# AMS_balancing.net
KiCad netlist of a schematic drawn in Altium Designer
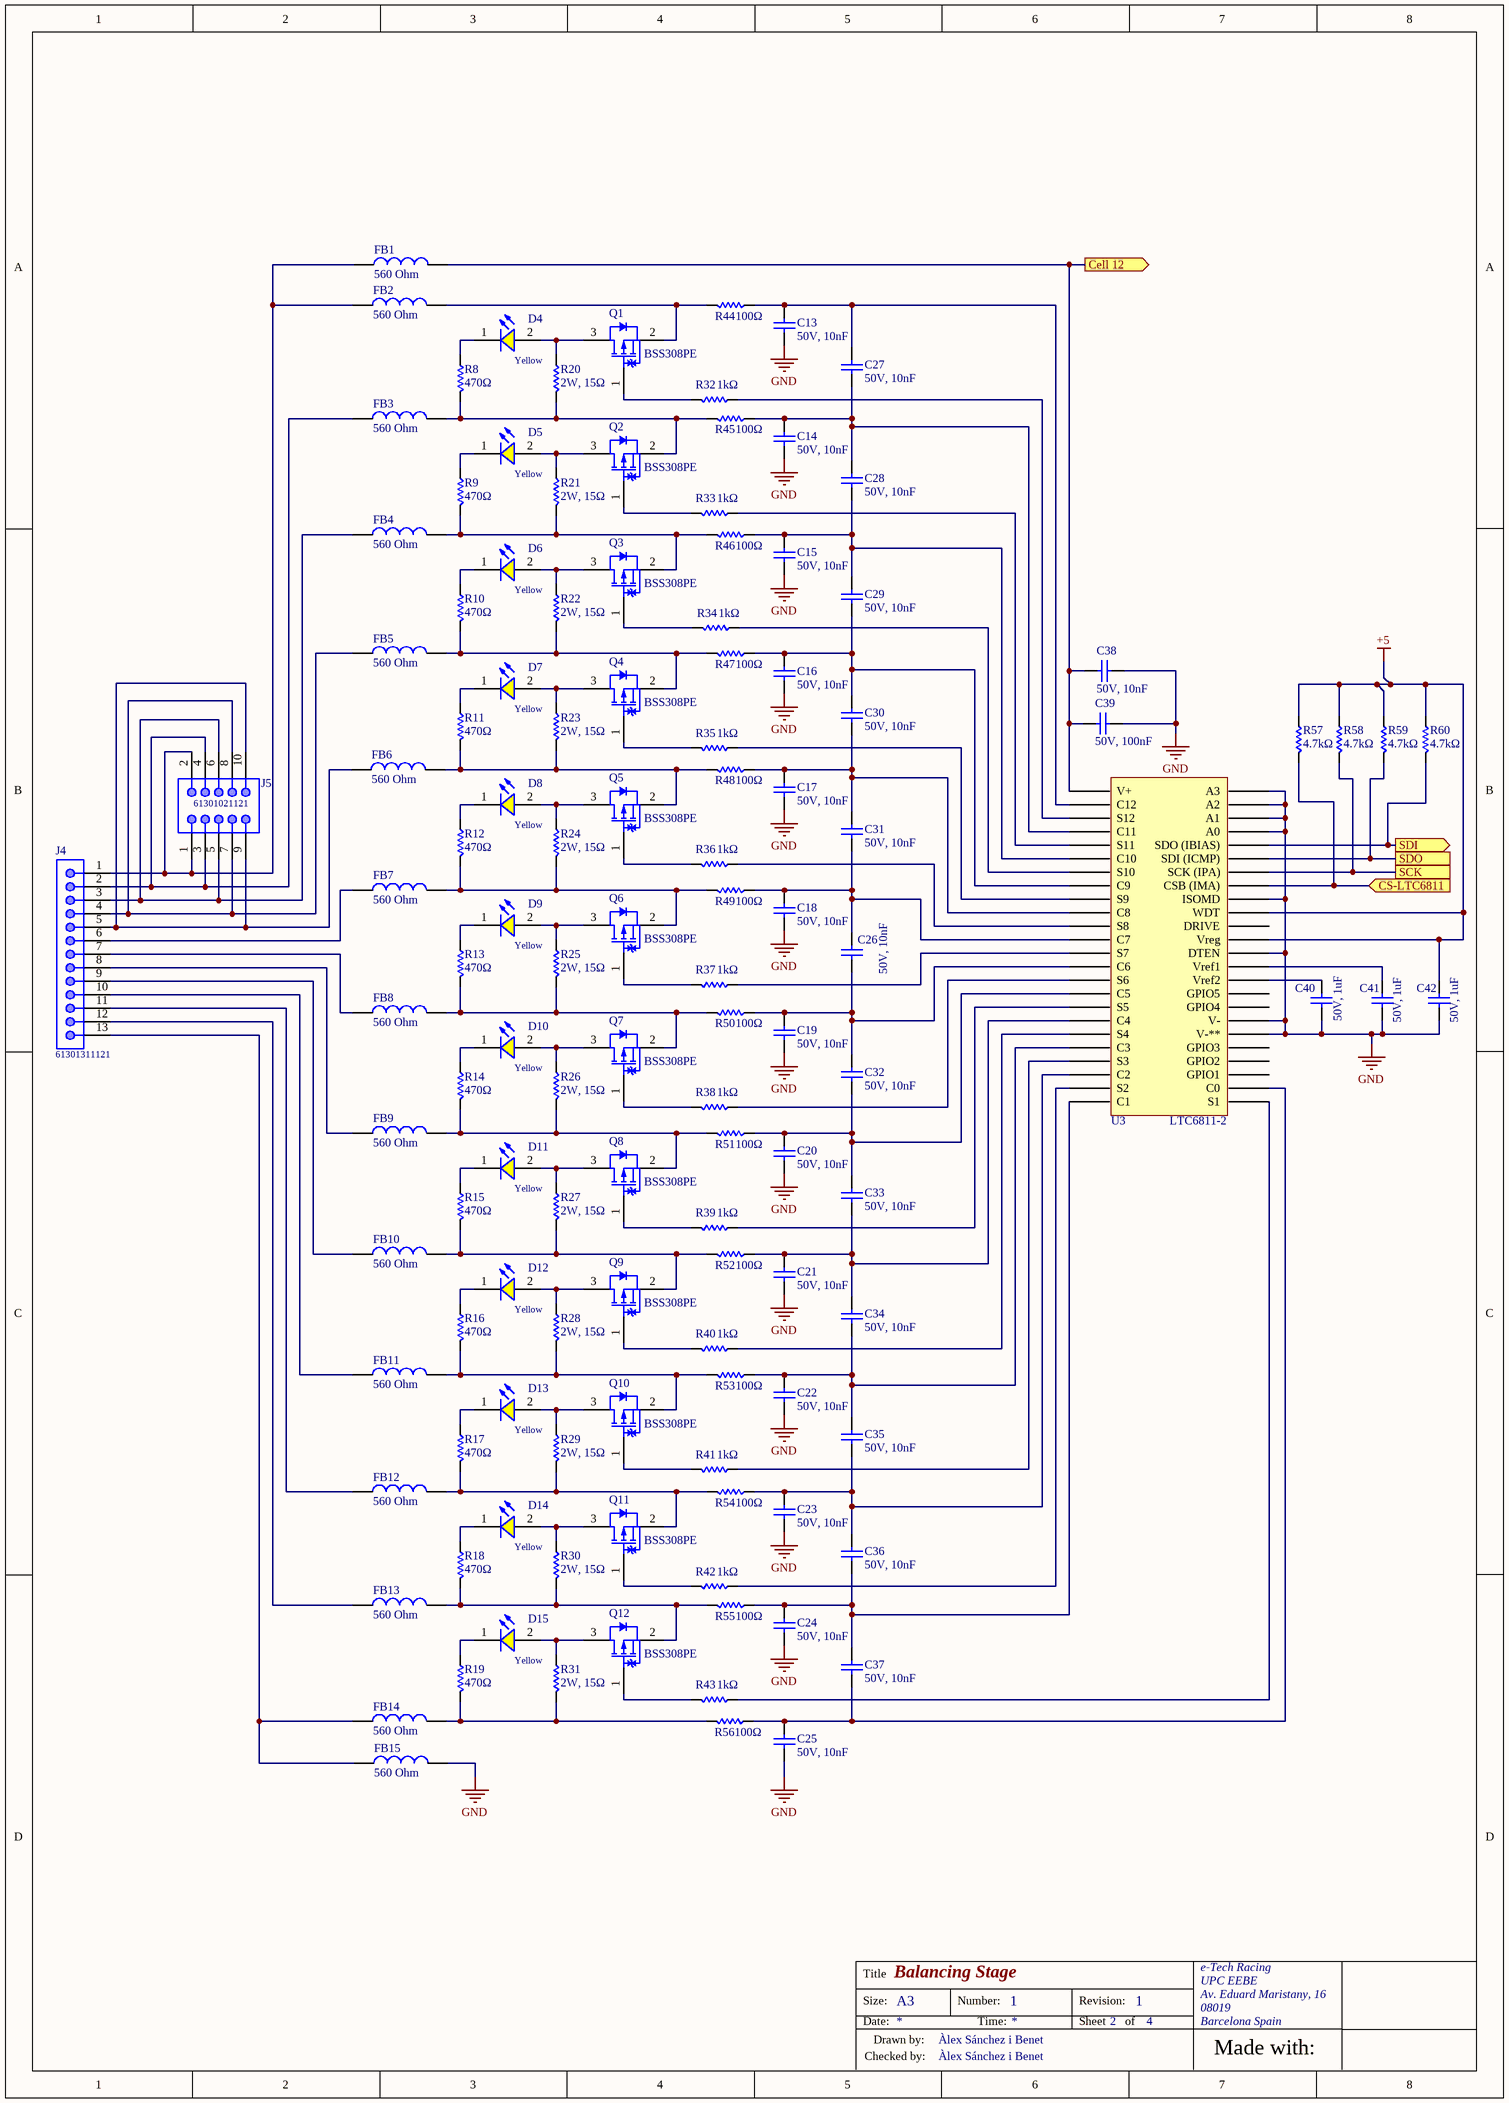
[diagram p0: AMS_balancing.SchDoc]

(export (version "E")
  (design (tool "Eeschema 10.0.6"))
  (components
    (comp (ref "C13")
      (value "50V, 10nF")
      (footprint "0805_2x1.25x0.8mm_Reflow Soldering")
      (description "WCAP-CSGP Ceramic Capacitors, 0805, X7R, 50V, 10nF")
      (fields (field (name "PART NUMBER") "885012207092") (field (name "PUBLISHER") "Wurth Elektronik"))
      (libsource (lib "Components_Library") (part "885012207092"))
    )
    (comp (ref "C14")
      (value "50V, 10nF")
      (footprint "0805_2x1.25x0.8mm_Reflow Soldering")
      (description "WCAP-CSGP Ceramic Capacitors, 0805, X7R, 50V, 10nF")
      (fields (field (name "PART NUMBER") "885012207092") (field (name "PUBLISHER") "Wurth Elektronik"))
      (libsource (lib "Components_Library") (part "885012207092"))
    )
    (comp (ref "C15")
      (value "50V, 10nF")
      (footprint "0805_2x1.25x0.8mm_Reflow Soldering")
      (description "WCAP-CSGP Ceramic Capacitors, 0805, X7R, 50V, 10nF")
      (fields (field (name "PART NUMBER") "885012207092") (field (name "PUBLISHER") "Wurth Elektronik"))
      (libsource (lib "Components_Library") (part "885012207092"))
    )
    (comp (ref "C16")
      (value "50V, 10nF")
      (footprint "0805_2x1.25x0.8mm_Reflow Soldering")
      (description "WCAP-CSGP Ceramic Capacitors, 0805, X7R, 50V, 10nF")
      (fields (field (name "PART NUMBER") "885012207092") (field (name "PUBLISHER") "Wurth Elektronik"))
      (libsource (lib "Components_Library") (part "885012207092"))
    )
    (comp (ref "C17")
      (value "50V, 10nF")
      (footprint "0805_2x1.25x0.8mm_Reflow Soldering")
      (description "WCAP-CSGP Ceramic Capacitors, 0805, X7R, 50V, 10nF")
      (fields (field (name "PART NUMBER") "885012207092") (field (name "PUBLISHER") "Wurth Elektronik"))
      (libsource (lib "Components_Library") (part "885012207092"))
    )
    (comp (ref "C18")
      (value "50V, 10nF")
      (footprint "0805_2x1.25x0.8mm_Reflow Soldering")
      (description "WCAP-CSGP Ceramic Capacitors, 0805, X7R, 50V, 10nF")
      (fields (field (name "PART NUMBER") "885012207092") (field (name "PUBLISHER") "Wurth Elektronik"))
      (libsource (lib "Components_Library") (part "885012207092"))
    )
    (comp (ref "C19")
      (value "50V, 10nF")
      (footprint "0805_2x1.25x0.8mm_Reflow Soldering")
      (description "WCAP-CSGP Ceramic Capacitors, 0805, X7R, 50V, 10nF")
      (fields (field (name "PART NUMBER") "885012207092") (field (name "PUBLISHER") "Wurth Elektronik"))
      (libsource (lib "Components_Library") (part "885012207092"))
    )
    (comp (ref "C20")
      (value "50V, 10nF")
      (footprint "0805_2x1.25x0.8mm_Reflow Soldering")
      (description "WCAP-CSGP Ceramic Capacitors, 0805, X7R, 50V, 10nF")
      (fields (field (name "PART NUMBER") "885012207092") (field (name "PUBLISHER") "Wurth Elektronik"))
      (libsource (lib "Components_Library") (part "885012207092"))
    )
    (comp (ref "C21")
      (value "50V, 10nF")
      (footprint "0805_2x1.25x0.8mm_Reflow Soldering")
      (description "WCAP-CSGP Ceramic Capacitors, 0805, X7R, 50V, 10nF")
      (fields (field (name "PART NUMBER") "885012207092") (field (name "PUBLISHER") "Wurth Elektronik"))
      (libsource (lib "Components_Library") (part "885012207092"))
    )
    (comp (ref "C22")
      (value "50V, 10nF")
      (footprint "0805_2x1.25x0.8mm_Reflow Soldering")
      (description "WCAP-CSGP Ceramic Capacitors, 0805, X7R, 50V, 10nF")
      (fields (field (name "PART NUMBER") "885012207092") (field (name "PUBLISHER") "Wurth Elektronik"))
      (libsource (lib "Components_Library") (part "885012207092"))
    )
    (comp (ref "C23")
      (value "50V, 10nF")
      (footprint "0805_2x1.25x0.8mm_Reflow Soldering")
      (description "WCAP-CSGP Ceramic Capacitors, 0805, X7R, 50V, 10nF")
      (fields (field (name "PART NUMBER") "885012207092") (field (name "PUBLISHER") "Wurth Elektronik"))
      (libsource (lib "Components_Library") (part "885012207092"))
    )
    (comp (ref "C24")
      (value "50V, 10nF")
      (footprint "0805_2x1.25x0.8mm_Reflow Soldering")
      (description "WCAP-CSGP Ceramic Capacitors, 0805, X7R, 50V, 10nF")
      (fields (field (name "PART NUMBER") "885012207092") (field (name "PUBLISHER") "Wurth Elektronik"))
      (libsource (lib "Components_Library") (part "885012207092"))
    )
    (comp (ref "C25")
      (value "50V, 10nF")
      (footprint "0805_2x1.25x0.8mm_Reflow Soldering")
      (description "WCAP-CSGP Ceramic Capacitors, 0805, X7R, 50V, 10nF")
      (fields (field (name "PART NUMBER") "885012207092") (field (name "PUBLISHER") "Wurth Elektronik"))
      (libsource (lib "Components_Library") (part "885012207092"))
    )
    (comp (ref "C26")
      (value "50V, 10nF")
      (footprint "0805_2x1.25x0.8mm_Reflow Soldering")
      (description "WCAP-CSGP Ceramic Capacitors, 0805, X7R, 50V, 10nF")
      (fields (field (name "PART NUMBER") "885012207092") (field (name "PUBLISHER") "Wurth Elektronik"))
      (libsource (lib "Components_Library") (part "885012207092"))
    )
    (comp (ref "C27")
      (value "50V, 10nF")
      (footprint "0805_2x1.25x0.8mm_Reflow Soldering")
      (description "WCAP-CSGP Ceramic Capacitors, 0805, X7R, 50V, 10nF")
      (fields (field (name "PART NUMBER") "885012207092") (field (name "PUBLISHER") "Wurth Elektronik"))
      (libsource (lib "Components_Library") (part "885012207092"))
    )
    (comp (ref "C28")
      (value "50V, 10nF")
      (footprint "0805_2x1.25x0.8mm_Reflow Soldering")
      (description "WCAP-CSGP Ceramic Capacitors, 0805, X7R, 50V, 10nF")
      (fields (field (name "PART NUMBER") "885012207092") (field (name "PUBLISHER") "Wurth Elektronik"))
      (libsource (lib "Components_Library") (part "885012207092"))
    )
    (comp (ref "C29")
      (value "50V, 10nF")
      (footprint "0805_2x1.25x0.8mm_Reflow Soldering")
      (description "WCAP-CSGP Ceramic Capacitors, 0805, X7R, 50V, 10nF")
      (fields (field (name "PART NUMBER") "885012207092") (field (name "PUBLISHER") "Wurth Elektronik"))
      (libsource (lib "Components_Library") (part "885012207092"))
    )
    (comp (ref "C30")
      (value "50V, 10nF")
      (footprint "0805_2x1.25x0.8mm_Reflow Soldering")
      (description "WCAP-CSGP Ceramic Capacitors, 0805, X7R, 50V, 10nF")
      (fields (field (name "PART NUMBER") "885012207092") (field (name "PUBLISHER") "Wurth Elektronik"))
      (libsource (lib "Components_Library") (part "885012207092"))
    )
    (comp (ref "C31")
      (value "50V, 10nF")
      (footprint "0805_2x1.25x0.8mm_Reflow Soldering")
      (description "WCAP-CSGP Ceramic Capacitors, 0805, X7R, 50V, 10nF")
      (fields (field (name "PART NUMBER") "885012207092") (field (name "PUBLISHER") "Wurth Elektronik"))
      (libsource (lib "Components_Library") (part "885012207092"))
    )
    (comp (ref "C32")
      (value "50V, 10nF")
      (footprint "0805_2x1.25x0.8mm_Reflow Soldering")
      (description "WCAP-CSGP Ceramic Capacitors, 0805, X7R, 50V, 10nF")
      (fields (field (name "PART NUMBER") "885012207092") (field (name "PUBLISHER") "Wurth Elektronik"))
      (libsource (lib "Components_Library") (part "885012207092"))
    )
    (comp (ref "C33")
      (value "50V, 10nF")
      (footprint "0805_2x1.25x0.8mm_Reflow Soldering")
      (description "WCAP-CSGP Ceramic Capacitors, 0805, X7R, 50V, 10nF")
      (fields (field (name "PART NUMBER") "885012207092") (field (name "PUBLISHER") "Wurth Elektronik"))
      (libsource (lib "Components_Library") (part "885012207092"))
    )
    (comp (ref "C34")
      (value "50V, 10nF")
      (footprint "0805_2x1.25x0.8mm_Reflow Soldering")
      (description "WCAP-CSGP Ceramic Capacitors, 0805, X7R, 50V, 10nF")
      (fields (field (name "PART NUMBER") "885012207092") (field (name "PUBLISHER") "Wurth Elektronik"))
      (libsource (lib "Components_Library") (part "885012207092"))
    )
    (comp (ref "C35")
      (value "50V, 10nF")
      (footprint "0805_2x1.25x0.8mm_Reflow Soldering")
      (description "WCAP-CSGP Ceramic Capacitors, 0805, X7R, 50V, 10nF")
      (fields (field (name "PART NUMBER") "885012207092") (field (name "PUBLISHER") "Wurth Elektronik"))
      (libsource (lib "Components_Library") (part "885012207092"))
    )
    (comp (ref "C36")
      (value "50V, 10nF")
      (footprint "0805_2x1.25x0.8mm_Reflow Soldering")
      (description "WCAP-CSGP Ceramic Capacitors, 0805, X7R, 50V, 10nF")
      (fields (field (name "PART NUMBER") "885012207092") (field (name "PUBLISHER") "Wurth Elektronik"))
      (libsource (lib "Components_Library") (part "885012207092"))
    )
    (comp (ref "C37")
      (value "50V, 10nF")
      (footprint "0805_2x1.25x0.8mm_Reflow Soldering")
      (description "WCAP-CSGP Ceramic Capacitors, 0805, X7R, 50V, 10nF")
      (fields (field (name "PART NUMBER") "885012207092") (field (name "PUBLISHER") "Wurth Elektronik"))
      (libsource (lib "Components_Library") (part "885012207092"))
    )
    (comp (ref "C38")
      (value "50V, 10nF")
      (footprint "0805_2x1.25x0.8mm_Reflow Soldering")
      (description "WCAP-CSGP Ceramic Capacitors, 0805, X7R, 50V, 10nF")
      (fields (field (name "PART NUMBER") "885012207092") (field (name "PUBLISHER") "Wurth Elektronik"))
      (libsource (lib "Components_Library") (part "885012207092"))
    )
    (comp (ref "C39")
      (value "50V, 100nF")
      (footprint "0805_2x1.25x0.8mm_Reflow Soldering")
      (description "WCAP-CSGP Ceramic Capacitors, 0805, X7R, 50V, 100nF")
      (fields (field (name "PART NUMBER") "885012207098") (field (name "PUBLISHER") "Wurth Elektronik"))
      (libsource (lib "Components_Library") (part "885012207098"))
    )
    (comp (ref "C40")
      (value "50V, 1uF")
      (footprint "0805_2x1.25x1.25mm_Reflow Soldering")
      (description "WCAP-CSGP Ceramic Capacitors, 0805, X7R, 50V, 1uF")
      (fields (field (name "PART NUMBER") "885012207103") (field (name "PUBLISHER") "Wurth Elektronik"))
      (libsource (lib "Components_Library") (part "885012207103"))
    )
    (comp (ref "C41")
      (value "50V, 1uF")
      (footprint "0805_2x1.25x1.25mm_Reflow Soldering")
      (description "WCAP-CSGP Ceramic Capacitors, 0805, X7R, 50V, 1uF")
      (fields (field (name "PART NUMBER") "885012207103") (field (name "PUBLISHER") "Wurth Elektronik"))
      (libsource (lib "Components_Library") (part "885012207103"))
    )
    (comp (ref "C42")
      (value "50V, 1uF")
      (footprint "0805_2x1.25x1.25mm_Reflow Soldering")
      (description "WCAP-CSGP Ceramic Capacitors, 0805, X7R, 50V, 1uF")
      (fields (field (name "PART NUMBER") "885012207103") (field (name "PUBLISHER") "Wurth Elektronik"))
      (libsource (lib "Components_Library") (part "885012207103"))
    )
    (comp (ref "D4")
      (value "Yellow")
      (footprint "WL-SMCW_0805")
      (description "SMT Mono-color Chip LED Waterclear WL-SMCW, size 0805, Yellow, 2 V, 140 deg, 120 mcd")
      (fields (field (name "PART NUMBER") "150080YS75000") (field (name "PUBLISHER") "Wurth Elektronik"))
      (libsource (lib "Components_Library") (part "150080YS75000"))
    )
    (comp (ref "D5")
      (value "Yellow")
      (footprint "WL-SMCW_0805")
      (description "SMT Mono-color Chip LED Waterclear WL-SMCW, size 0805, Yellow, 2 V, 140 deg, 120 mcd")
      (fields (field (name "PART NUMBER") "150080YS75000") (field (name "PUBLISHER") "Wurth Elektronik"))
      (libsource (lib "Components_Library") (part "150080YS75000"))
    )
    (comp (ref "D6")
      (value "Yellow")
      (footprint "WL-SMCW_0805")
      (description "SMT Mono-color Chip LED Waterclear WL-SMCW, size 0805, Yellow, 2 V, 140 deg, 120 mcd")
      (fields (field (name "PART NUMBER") "150080YS75000") (field (name "PUBLISHER") "Wurth Elektronik"))
      (libsource (lib "Components_Library") (part "150080YS75000"))
    )
    (comp (ref "D7")
      (value "Yellow")
      (footprint "WL-SMCW_0805")
      (description "SMT Mono-color Chip LED Waterclear WL-SMCW, size 0805, Yellow, 2 V, 140 deg, 120 mcd")
      (fields (field (name "PART NUMBER") "150080YS75000") (field (name "PUBLISHER") "Wurth Elektronik"))
      (libsource (lib "Components_Library") (part "150080YS75000"))
    )
    (comp (ref "D8")
      (value "Yellow")
      (footprint "WL-SMCW_0805")
      (description "SMT Mono-color Chip LED Waterclear WL-SMCW, size 0805, Yellow, 2 V, 140 deg, 120 mcd")
      (fields (field (name "PART NUMBER") "150080YS75000") (field (name "PUBLISHER") "Wurth Elektronik"))
      (libsource (lib "Components_Library") (part "150080YS75000"))
    )
    (comp (ref "D9")
      (value "Yellow")
      (footprint "WL-SMCW_0805")
      (description "SMT Mono-color Chip LED Waterclear WL-SMCW, size 0805, Yellow, 2 V, 140 deg, 120 mcd")
      (fields (field (name "PART NUMBER") "150080YS75000") (field (name "PUBLISHER") "Wurth Elektronik"))
      (libsource (lib "Components_Library") (part "150080YS75000"))
    )
    (comp (ref "D10")
      (value "Yellow")
      (footprint "WL-SMCW_0805")
      (description "SMT Mono-color Chip LED Waterclear WL-SMCW, size 0805, Yellow, 2 V, 140 deg, 120 mcd")
      (fields (field (name "PART NUMBER") "150080YS75000") (field (name "PUBLISHER") "Wurth Elektronik"))
      (libsource (lib "Components_Library") (part "150080YS75000"))
    )
    (comp (ref "D11")
      (value "Yellow")
      (footprint "WL-SMCW_0805")
      (description "SMT Mono-color Chip LED Waterclear WL-SMCW, size 0805, Yellow, 2 V, 140 deg, 120 mcd")
      (fields (field (name "PART NUMBER") "150080YS75000") (field (name "PUBLISHER") "Wurth Elektronik"))
      (libsource (lib "Components_Library") (part "150080YS75000"))
    )
    (comp (ref "D12")
      (value "Yellow")
      (footprint "WL-SMCW_0805")
      (description "SMT Mono-color Chip LED Waterclear WL-SMCW, size 0805, Yellow, 2 V, 140 deg, 120 mcd")
      (fields (field (name "PART NUMBER") "150080YS75000") (field (name "PUBLISHER") "Wurth Elektronik"))
      (libsource (lib "Components_Library") (part "150080YS75000"))
    )
    (comp (ref "D13")
      (value "Yellow")
      (footprint "WL-SMCW_0805")
      (description "SMT Mono-color Chip LED Waterclear WL-SMCW, size 0805, Yellow, 2 V, 140 deg, 120 mcd")
      (fields (field (name "PART NUMBER") "150080YS75000") (field (name "PUBLISHER") "Wurth Elektronik"))
      (libsource (lib "Components_Library") (part "150080YS75000"))
    )
    (comp (ref "D14")
      (value "Yellow")
      (footprint "WL-SMCW_0805")
      (description "SMT Mono-color Chip LED Waterclear WL-SMCW, size 0805, Yellow, 2 V, 140 deg, 120 mcd")
      (fields (field (name "PART NUMBER") "150080YS75000") (field (name "PUBLISHER") "Wurth Elektronik"))
      (libsource (lib "Components_Library") (part "150080YS75000"))
    )
    (comp (ref "D15")
      (value "Yellow")
      (footprint "WL-SMCW_0805")
      (description "SMT Mono-color Chip LED Waterclear WL-SMCW, size 0805, Yellow, 2 V, 140 deg, 120 mcd")
      (fields (field (name "PART NUMBER") "150080YS75000") (field (name "PUBLISHER") "Wurth Elektronik"))
      (libsource (lib "Components_Library") (part "150080YS75000"))
    )
    (comp (ref "FB1")
      (value "560 Ohm")
      (footprint "0805_High Current")
      (description "WE-CBA SMD EMI Suppression Ferrite Bead, 0805, High Current, 1.5 A, 560 Ohm")
      (fields (field (name "PART NUMBER") "782853561") (field (name "PUBLISHER") "Wurth Elektronik"))
      (libsource (lib "Components_Library") (part "782853561"))
    )
    (comp (ref "FB2")
      (value "560 Ohm")
      (footprint "0805_High Current")
      (description "WE-CBA SMD EMI Suppression Ferrite Bead, 0805, High Current, 1.5 A, 560 Ohm")
      (fields (field (name "PART NUMBER") "782853561") (field (name "PUBLISHER") "Wurth Elektronik"))
      (libsource (lib "Components_Library") (part "782853561"))
    )
    (comp (ref "FB3")
      (value "560 Ohm")
      (footprint "0805_High Current")
      (description "WE-CBA SMD EMI Suppression Ferrite Bead, 0805, High Current, 1.5 A, 560 Ohm")
      (fields (field (name "PART NUMBER") "782853561") (field (name "PUBLISHER") "Wurth Elektronik"))
      (libsource (lib "Components_Library") (part "782853561"))
    )
    (comp (ref "FB4")
      (value "560 Ohm")
      (footprint "0805_High Current")
      (description "WE-CBA SMD EMI Suppression Ferrite Bead, 0805, High Current, 1.5 A, 560 Ohm")
      (fields (field (name "PART NUMBER") "782853561") (field (name "PUBLISHER") "Wurth Elektronik"))
      (libsource (lib "Components_Library") (part "782853561"))
    )
    (comp (ref "FB5")
      (value "560 Ohm")
      (footprint "0805_High Current")
      (description "WE-CBA SMD EMI Suppression Ferrite Bead, 0805, High Current, 1.5 A, 560 Ohm")
      (fields (field (name "PART NUMBER") "782853561") (field (name "PUBLISHER") "Wurth Elektronik"))
      (libsource (lib "Components_Library") (part "782853561"))
    )
    (comp (ref "FB6")
      (value "560 Ohm")
      (footprint "0805_High Current")
      (description "WE-CBA SMD EMI Suppression Ferrite Bead, 0805, High Current, 1.5 A, 560 Ohm")
      (fields (field (name "PART NUMBER") "782853561") (field (name "PUBLISHER") "Wurth Elektronik"))
      (libsource (lib "Components_Library") (part "782853561"))
    )
    (comp (ref "FB7")
      (value "560 Ohm")
      (footprint "0805_High Current")
      (description "WE-CBA SMD EMI Suppression Ferrite Bead, 0805, High Current, 1.5 A, 560 Ohm")
      (fields (field (name "PART NUMBER") "782853561") (field (name "PUBLISHER") "Wurth Elektronik"))
      (libsource (lib "Components_Library") (part "782853561"))
    )
    (comp (ref "FB8")
      (value "560 Ohm")
      (footprint "0805_High Current")
      (description "WE-CBA SMD EMI Suppression Ferrite Bead, 0805, High Current, 1.5 A, 560 Ohm")
      (fields (field (name "PART NUMBER") "782853561") (field (name "PUBLISHER") "Wurth Elektronik"))
      (libsource (lib "Components_Library") (part "782853561"))
    )
    (comp (ref "FB9")
      (value "560 Ohm")
      (footprint "0805_High Current")
      (description "WE-CBA SMD EMI Suppression Ferrite Bead, 0805, High Current, 1.5 A, 560 Ohm")
      (fields (field (name "PART NUMBER") "782853561") (field (name "PUBLISHER") "Wurth Elektronik"))
      (libsource (lib "Components_Library") (part "782853561"))
    )
    (comp (ref "FB10")
      (value "560 Ohm")
      (footprint "0805_High Current")
      (description "WE-CBA SMD EMI Suppression Ferrite Bead, 0805, High Current, 1.5 A, 560 Ohm")
      (fields (field (name "PART NUMBER") "782853561") (field (name "PUBLISHER") "Wurth Elektronik"))
      (libsource (lib "Components_Library") (part "782853561"))
    )
    (comp (ref "FB11")
      (value "560 Ohm")
      (footprint "0805_High Current")
      (description "WE-CBA SMD EMI Suppression Ferrite Bead, 0805, High Current, 1.5 A, 560 Ohm")
      (fields (field (name "PART NUMBER") "782853561") (field (name "PUBLISHER") "Wurth Elektronik"))
      (libsource (lib "Components_Library") (part "782853561"))
    )
    (comp (ref "FB12")
      (value "560 Ohm")
      (footprint "0805_High Current")
      (description "WE-CBA SMD EMI Suppression Ferrite Bead, 0805, High Current, 1.5 A, 560 Ohm")
      (fields (field (name "PART NUMBER") "782853561") (field (name "PUBLISHER") "Wurth Elektronik"))
      (libsource (lib "Components_Library") (part "782853561"))
    )
    (comp (ref "FB13")
      (value "560 Ohm")
      (footprint "0805_High Current")
      (description "WE-CBA SMD EMI Suppression Ferrite Bead, 0805, High Current, 1.5 A, 560 Ohm")
      (fields (field (name "PART NUMBER") "782853561") (field (name "PUBLISHER") "Wurth Elektronik"))
      (libsource (lib "Components_Library") (part "782853561"))
    )
    (comp (ref "FB14")
      (value "560 Ohm")
      (footprint "0805_High Current")
      (description "WE-CBA SMD EMI Suppression Ferrite Bead, 0805, High Current, 1.5 A, 560 Ohm")
      (fields (field (name "PART NUMBER") "782853561") (field (name "PUBLISHER") "Wurth Elektronik"))
      (libsource (lib "Components_Library") (part "782853561"))
    )
    (comp (ref "FB15")
      (value "560 Ohm")
      (footprint "0805_High Current")
      (description "WE-CBA SMD EMI Suppression Ferrite Bead, 0805, High Current, 1.5 A, 560 Ohm")
      (fields (field (name "PART NUMBER") "782853561") (field (name "PUBLISHER") "Wurth Elektronik"))
      (libsource (lib "Components_Library") (part "782853561"))
    )
    (comp (ref "J4")
      (value "61301311121")
      (footprint "61301311121-bottom")
      (description "THT Vertical Pin Header WR-PHD, Pitch 2.54 mm, Single Row, 13 pins")
      (fields (field (name "PUBLISHER") "Wurth Elektronik"))
      (libsource (lib "Components_Library") (part "61301311121"))
    )
    (comp (ref "J5")
      (value "61301021121")
      (footprint "61301021121")
      (description "THT Vertical Pin Header WR-PHD, Pitch 2.54 mm, Dual Row, 10 pins")
      (fields (field (name "PUBLISHER") "Wurth Elektronik"))
      (libsource (lib "Components_Library") (part "61301021121"))
    )
    (comp (ref "Q1")
      (value "BSS308PE")
      (footprint "INF-PG-SOT23_N")
      (fields (field (name "MANUFACTURER") "Infineon"))
      (libsource (lib "Components_Library") (part "BSS308PE"))
    )
    (comp (ref "Q2")
      (value "BSS308PE")
      (footprint "INF-PG-SOT23_N")
      (fields (field (name "MANUFACTURER") "Infineon"))
      (libsource (lib "Components_Library") (part "BSS308PE"))
    )
    (comp (ref "Q3")
      (value "BSS308PE")
      (footprint "INF-PG-SOT23_N")
      (fields (field (name "MANUFACTURER") "Infineon"))
      (libsource (lib "Components_Library") (part "BSS308PE"))
    )
    (comp (ref "Q4")
      (value "BSS308PE")
      (footprint "INF-PG-SOT23_N")
      (fields (field (name "MANUFACTURER") "Infineon"))
      (libsource (lib "Components_Library") (part "BSS308PE"))
    )
    (comp (ref "Q5")
      (value "BSS308PE")
      (footprint "INF-PG-SOT23_N")
      (fields (field (name "MANUFACTURER") "Infineon"))
      (libsource (lib "Components_Library") (part "BSS308PE"))
    )
    (comp (ref "Q6")
      (value "BSS308PE")
      (footprint "INF-PG-SOT23_N")
      (fields (field (name "MANUFACTURER") "Infineon"))
      (libsource (lib "Components_Library") (part "BSS308PE"))
    )
    (comp (ref "Q7")
      (value "BSS308PE")
      (footprint "INF-PG-SOT23_N")
      (fields (field (name "MANUFACTURER") "Infineon"))
      (libsource (lib "Components_Library") (part "BSS308PE"))
    )
    (comp (ref "Q8")
      (value "BSS308PE")
      (footprint "INF-PG-SOT23_N")
      (fields (field (name "MANUFACTURER") "Infineon"))
      (libsource (lib "Components_Library") (part "BSS308PE"))
    )
    (comp (ref "Q9")
      (value "BSS308PE")
      (footprint "INF-PG-SOT23_N")
      (fields (field (name "MANUFACTURER") "Infineon"))
      (libsource (lib "Components_Library") (part "BSS308PE"))
    )
    (comp (ref "Q10")
      (value "BSS308PE")
      (footprint "INF-PG-SOT23_N")
      (fields (field (name "MANUFACTURER") "Infineon"))
      (libsource (lib "Components_Library") (part "BSS308PE"))
    )
    (comp (ref "Q11")
      (value "BSS308PE")
      (footprint "INF-PG-SOT23_N")
      (fields (field (name "MANUFACTURER") "Infineon"))
      (libsource (lib "Components_Library") (part "BSS308PE"))
    )
    (comp (ref "Q12")
      (value "BSS308PE")
      (footprint "INF-PG-SOT23_N")
      (fields (field (name "MANUFACTURER") "Infineon"))
      (libsource (lib "Components_Library") (part "BSS308PE"))
    )
    (comp (ref "R8")
      (value "470Ω")
      (footprint "CR0805")
      (description "Chip Resistor 0805")
      (fields (field (name "MANUFACTURER") "Bourns"))
      (libsource (lib "Components_Library") (part "CR0805-FX-4700GLF"))
    )
    (comp (ref "R9")
      (value "470Ω")
      (footprint "CR0805")
      (description "Chip Resistor 0805")
      (fields (field (name "MANUFACTURER") "Bourns"))
      (libsource (lib "Components_Library") (part "CR0805-FX-4700GLF"))
    )
    (comp (ref "R10")
      (value "470Ω")
      (footprint "CR0805")
      (description "Chip Resistor 0805")
      (fields (field (name "MANUFACTURER") "Bourns"))
      (libsource (lib "Components_Library") (part "CR0805-FX-4700GLF"))
    )
    (comp (ref "R11")
      (value "470Ω")
      (footprint "CR0805")
      (description "Chip Resistor 0805")
      (fields (field (name "MANUFACTURER") "Bourns"))
      (libsource (lib "Components_Library") (part "CR0805-FX-4700GLF"))
    )
    (comp (ref "R12")
      (value "470Ω")
      (footprint "CR0805")
      (description "Chip Resistor 0805")
      (fields (field (name "MANUFACTURER") "Bourns"))
      (libsource (lib "Components_Library") (part "CR0805-FX-4700GLF"))
    )
    (comp (ref "R13")
      (value "470Ω")
      (footprint "CR0805")
      (description "Chip Resistor 0805")
      (fields (field (name "MANUFACTURER") "Bourns"))
      (libsource (lib "Components_Library") (part "CR0805-FX-4700GLF"))
    )
    (comp (ref "R14")
      (value "470Ω")
      (footprint "CR0805")
      (description "Chip Resistor 0805")
      (fields (field (name "MANUFACTURER") "Bourns"))
      (libsource (lib "Components_Library") (part "CR0805-FX-4700GLF"))
    )
    (comp (ref "R15")
      (value "470Ω")
      (footprint "CR0805")
      (description "Chip Resistor 0805")
      (fields (field (name "MANUFACTURER") "Bourns"))
      (libsource (lib "Components_Library") (part "CR0805-FX-4700GLF"))
    )
    (comp (ref "R16")
      (value "470Ω")
      (footprint "CR0805")
      (description "Chip Resistor 0805")
      (fields (field (name "MANUFACTURER") "Bourns"))
      (libsource (lib "Components_Library") (part "CR0805-FX-4700GLF"))
    )
    (comp (ref "R17")
      (value "470Ω")
      (footprint "CR0805")
      (description "Chip Resistor 0805")
      (fields (field (name "MANUFACTURER") "Bourns"))
      (libsource (lib "Components_Library") (part "CR0805-FX-4700GLF"))
    )
    (comp (ref "R18")
      (value "470Ω")
      (footprint "CR0805")
      (description "Chip Resistor 0805")
      (fields (field (name "MANUFACTURER") "Bourns"))
      (libsource (lib "Components_Library") (part "CR0805-FX-4700GLF"))
    )
    (comp (ref "R19")
      (value "470Ω")
      (footprint "CR0805")
      (description "Chip Resistor 0805")
      (fields (field (name "MANUFACTURER") "Bourns"))
      (libsource (lib "Components_Library") (part "CR0805-FX-4700GLF"))
    )
    (comp (ref "R20")
      (value "2W, 15Ω")
      (footprint "352115RFT")
      (description "SMD Power Resistor, Type 3521 Series")
      (fields (field (name "MANUFACTURER") "TE Connectivity"))
      (libsource (lib "Components_Library") (part "352115RFT"))
    )
    (comp (ref "R21")
      (value "2W, 15Ω")
      (footprint "352115RFT")
      (description "SMD Power Resistor, Type 3521 Series")
      (fields (field (name "MANUFACTURER") "TE Connectivity"))
      (libsource (lib "Components_Library") (part "352115RFT"))
    )
    (comp (ref "R22")
      (value "2W, 15Ω")
      (footprint "352115RFT")
      (description "SMD Power Resistor, Type 3521 Series")
      (fields (field (name "MANUFACTURER") "TE Connectivity"))
      (libsource (lib "Components_Library") (part "352115RFT"))
    )
    (comp (ref "R23")
      (value "2W, 15Ω")
      (footprint "352115RFT")
      (description "SMD Power Resistor, Type 3521 Series")
      (fields (field (name "MANUFACTURER") "TE Connectivity"))
      (libsource (lib "Components_Library") (part "352115RFT"))
    )
    (comp (ref "R24")
      (value "2W, 15Ω")
      (footprint "352115RFT")
      (description "SMD Power Resistor, Type 3521 Series")
      (fields (field (name "MANUFACTURER") "TE Connectivity"))
      (libsource (lib "Components_Library") (part "352115RFT"))
    )
    (comp (ref "R25")
      (value "2W, 15Ω")
      (footprint "352115RFT")
      (description "SMD Power Resistor, Type 3521 Series")
      (fields (field (name "MANUFACTURER") "TE Connectivity"))
      (libsource (lib "Components_Library") (part "352115RFT"))
    )
    (comp (ref "R26")
      (value "2W, 15Ω")
      (footprint "352115RFT")
      (description "SMD Power Resistor, Type 3521 Series")
      (fields (field (name "MANUFACTURER") "TE Connectivity"))
      (libsource (lib "Components_Library") (part "352115RFT"))
    )
    (comp (ref "R27")
      (value "2W, 15Ω")
      (footprint "352115RFT")
      (description "SMD Power Resistor, Type 3521 Series")
      (fields (field (name "MANUFACTURER") "TE Connectivity"))
      (libsource (lib "Components_Library") (part "352115RFT"))
    )
    (comp (ref "R28")
      (value "2W, 15Ω")
      (footprint "352115RFT")
      (description "SMD Power Resistor, Type 3521 Series")
      (fields (field (name "MANUFACTURER") "TE Connectivity"))
      (libsource (lib "Components_Library") (part "352115RFT"))
    )
    (comp (ref "R29")
      (value "2W, 15Ω")
      (footprint "352115RFT")
      (description "SMD Power Resistor, Type 3521 Series")
      (fields (field (name "MANUFACTURER") "TE Connectivity"))
      (libsource (lib "Components_Library") (part "352115RFT"))
    )
    (comp (ref "R30")
      (value "2W, 15Ω")
      (footprint "352115RFT")
      (description "SMD Power Resistor, Type 3521 Series")
      (fields (field (name "MANUFACTURER") "TE Connectivity"))
      (libsource (lib "Components_Library") (part "352115RFT"))
    )
    (comp (ref "R31")
      (value "2W, 15Ω")
      (footprint "352115RFT")
      (description "SMD Power Resistor, Type 3521 Series")
      (fields (field (name "MANUFACTURER") "TE Connectivity"))
      (libsource (lib "Components_Library") (part "352115RFT"))
    )
    (comp (ref "R32")
      (value "1kΩ")
      (footprint "CR0805")
      (description "Chip Resistor 0805")
      (fields (field (name "MANUFACTURER") "Bourns"))
      (libsource (lib "Components_Library") (part "CR0805-JW-102ELF"))
    )
    (comp (ref "R33")
      (value "1kΩ")
      (footprint "CR0805")
      (description "Chip Resistor 0805")
      (fields (field (name "MANUFACTURER") "Bourns"))
      (libsource (lib "Components_Library") (part "CR0805-JW-102ELF"))
    )
    (comp (ref "R34")
      (value "1kΩ")
      (footprint "CR0805")
      (description "Chip Resistor 0805")
      (fields (field (name "MANUFACTURER") "Bourns"))
      (libsource (lib "Components_Library") (part "CR0805-JW-102ELF"))
    )
    (comp (ref "R35")
      (value "1kΩ")
      (footprint "CR0805")
      (description "Chip Resistor 0805")
      (fields (field (name "MANUFACTURER") "Bourns"))
      (libsource (lib "Components_Library") (part "CR0805-JW-102ELF"))
    )
    (comp (ref "R36")
      (value "1kΩ")
      (footprint "CR0805")
      (description "Chip Resistor 0805")
      (fields (field (name "MANUFACTURER") "Bourns"))
      (libsource (lib "Components_Library") (part "CR0805-JW-102ELF"))
    )
    (comp (ref "R37")
      (value "1kΩ")
      (footprint "CR0805")
      (description "Chip Resistor 0805")
      (fields (field (name "MANUFACTURER") "Bourns"))
      (libsource (lib "Components_Library") (part "CR0805-JW-102ELF"))
    )
    (comp (ref "R38")
      (value "1kΩ")
      (footprint "CR0805")
      (description "Chip Resistor 0805")
      (fields (field (name "MANUFACTURER") "Bourns"))
      (libsource (lib "Components_Library") (part "CR0805-JW-102ELF"))
    )
    (comp (ref "R39")
      (value "1kΩ")
      (footprint "CR0805")
      (description "Chip Resistor 0805")
      (fields (field (name "MANUFACTURER") "Bourns"))
      (libsource (lib "Components_Library") (part "CR0805-JW-102ELF"))
    )
    (comp (ref "R40")
      (value "1kΩ")
      (footprint "CR0805")
      (description "Chip Resistor 0805")
      (fields (field (name "MANUFACTURER") "Bourns"))
      (libsource (lib "Components_Library") (part "CR0805-JW-102ELF"))
    )
    (comp (ref "R41")
      (value "1kΩ")
      (footprint "CR0805")
      (description "Chip Resistor 0805")
      (fields (field (name "MANUFACTURER") "Bourns"))
      (libsource (lib "Components_Library") (part "CR0805-JW-102ELF"))
    )
    (comp (ref "R42")
      (value "1kΩ")
      (footprint "CR0805")
      (description "Chip Resistor 0805")
      (fields (field (name "MANUFACTURER") "Bourns"))
      (libsource (lib "Components_Library") (part "CR0805-JW-102ELF"))
    )
    (comp (ref "R43")
      (value "1kΩ")
      (footprint "CR0805")
      (description "Chip Resistor 0805")
      (fields (field (name "MANUFACTURER") "Bourns"))
      (libsource (lib "Components_Library") (part "CR0805-JW-102ELF"))
    )
    (comp (ref "R44")
      (value "100Ω")
      (footprint "CR0805")
      (description "Chip Resistor 0805")
      (fields (field (name "MANUFACTURER") "Bourns"))
      (libsource (lib "Components_Library") (part "CR0805-FX-1000ELF"))
    )
    (comp (ref "R45")
      (value "100Ω")
      (footprint "CR0805")
      (description "Chip Resistor 0805")
      (fields (field (name "MANUFACTURER") "Bourns"))
      (libsource (lib "Components_Library") (part "CR0805-FX-1000ELF"))
    )
    (comp (ref "R46")
      (value "100Ω")
      (footprint "CR0805")
      (description "Chip Resistor 0805")
      (fields (field (name "MANUFACTURER") "Bourns"))
      (libsource (lib "Components_Library") (part "CR0805-FX-1000ELF"))
    )
    (comp (ref "R47")
      (value "100Ω")
      (footprint "CR0805")
      (description "Chip Resistor 0805")
      (fields (field (name "MANUFACTURER") "Bourns"))
      (libsource (lib "Components_Library") (part "CR0805-FX-1000ELF"))
    )
    (comp (ref "R48")
      (value "100Ω")
      (footprint "CR0805")
      (description "Chip Resistor 0805")
      (fields (field (name "MANUFACTURER") "Bourns"))
      (libsource (lib "Components_Library") (part "CR0805-FX-1000ELF"))
    )
    (comp (ref "R49")
      (value "100Ω")
      (footprint "CR0805")
      (description "Chip Resistor 0805")
      (fields (field (name "MANUFACTURER") "Bourns"))
      (libsource (lib "Components_Library") (part "CR0805-FX-1000ELF"))
    )
    (comp (ref "R50")
      (value "100Ω")
      (footprint "CR0805")
      (description "Chip Resistor 0805")
      (fields (field (name "MANUFACTURER") "Bourns"))
      (libsource (lib "Components_Library") (part "CR0805-FX-1000ELF"))
    )
    (comp (ref "R51")
      (value "100Ω")
      (footprint "CR0805")
      (description "Chip Resistor 0805")
      (fields (field (name "MANUFACTURER") "Bourns"))
      (libsource (lib "Components_Library") (part "CR0805-FX-1000ELF"))
    )
    (comp (ref "R52")
      (value "100Ω")
      (footprint "CR0805")
      (description "Chip Resistor 0805")
      (fields (field (name "MANUFACTURER") "Bourns"))
      (libsource (lib "Components_Library") (part "CR0805-FX-1000ELF"))
    )
    (comp (ref "R53")
      (value "100Ω")
      (footprint "CR0805")
      (description "Chip Resistor 0805")
      (fields (field (name "MANUFACTURER") "Bourns"))
      (libsource (lib "Components_Library") (part "CR0805-FX-1000ELF"))
    )
    (comp (ref "R54")
      (value "100Ω")
      (footprint "CR0805")
      (description "Chip Resistor 0805")
      (fields (field (name "MANUFACTURER") "Bourns"))
      (libsource (lib "Components_Library") (part "CR0805-FX-1000ELF"))
    )
    (comp (ref "R55")
      (value "100Ω")
      (footprint "CR0805")
      (description "Chip Resistor 0805")
      (fields (field (name "MANUFACTURER") "Bourns"))
      (libsource (lib "Components_Library") (part "CR0805-FX-1000ELF"))
    )
    (comp (ref "R56")
      (value "100Ω")
      (footprint "CR0805")
      (description "Chip Resistor 0805")
      (fields (field (name "MANUFACTURER") "Bourns"))
      (libsource (lib "Components_Library") (part "CR0805-FX-1000ELF"))
    )
    (comp (ref "R57")
      (value "4.7kΩ")
      (footprint "CR0805")
      (description "Chip Resistor 0805")
      (fields (field (name "MANUFACTURER") "Bourns"))
      (libsource (lib "Components_Library") (part "CR0805-FX-4701GLF"))
    )
    (comp (ref "R58")
      (value "4.7kΩ")
      (footprint "CR0805")
      (description "Chip Resistor 0805")
      (fields (field (name "MANUFACTURER") "Bourns"))
      (libsource (lib "Components_Library") (part "CR0805-FX-4701GLF"))
    )
    (comp (ref "R59")
      (value "4.7kΩ")
      (footprint "CR0805")
      (description "Chip Resistor 0805")
      (fields (field (name "MANUFACTURER") "Bourns"))
      (libsource (lib "Components_Library") (part "CR0805-FX-4701GLF"))
    )
    (comp (ref "R60")
      (value "4.7kΩ")
      (footprint "CR0805")
      (description "Chip Resistor 0805")
      (fields (field (name "MANUFACTURER") "Bourns"))
      (libsource (lib "Components_Library") (part "CR0805-FX-4701GLF"))
    )
    (comp (ref "U3")
      (value "LTC6811-2")
      (footprint "LTC6811-2")
      (description "Multicell Battery Monitors")
      (fields (field (name "MANUFACTURER") "Analog Devices"))
      (libsource (lib "Components_Library") (part "LTC6811-2"))
    )
  )
  (nets
    (net (code "1") (name "+5") (class "Default")
      (node (ref "C42") (pin "2") (pinfunction "2_2") (pintype "passive"))
      (node (ref "R57") (pin "2") (pinfunction "2_2") (pintype "passive"))
      (node (ref "R58") (pin "2") (pinfunction "2_2") (pintype "passive"))
      (node (ref "R59") (pin "2") (pinfunction "2_2") (pintype "passive"))
      (node (ref "R60") (pin "2") (pinfunction "2_2") (pintype "passive"))
      (node (ref "U3") (pin "37") (pinfunction "Vreg_37") (pintype "passive"))
      (node (ref "U3") (pin "39") (pinfunction "WDT_39") (pintype "passive"))
    )
    (net (code "2") (name "/CS-LTC6811") (class "Default")
      (node (ref "R57") (pin "1") (pinfunction "1_1") (pintype "passive"))
      (node (ref "U3") (pin "41") (pinfunction "CSB_(IMA)_41") (pintype "passive"))
    )
    (net (code "3") (name "/Cell 12") (class "Default")
      (node (ref "C38") (pin "1") (pinfunction "1_1") (pintype "passive"))
      (node (ref "C39") (pin "1") (pinfunction "1_1") (pintype "passive"))
      (node (ref "FB1") (pin "2") (pinfunction "2_2") (pintype "passive"))
      (node (ref "U3") (pin "1") (pinfunction "V+_1") (pintype "passive"))
    )
    (net (code "4") (name "/SCK") (class "Default")
      (node (ref "R58") (pin "1") (pinfunction "1_1") (pintype "passive"))
      (node (ref "U3") (pin "42") (pinfunction "SCK_(IPA)_42") (pintype "passive"))
    )
    (net (code "5") (name "/SDI") (class "Default")
      (node (ref "R60") (pin "1") (pinfunction "1_1") (pintype "passive"))
      (node (ref "U3") (pin "44") (pinfunction "SDO_(IBIAS)_44") (pintype "passive"))
    )
    (net (code "6") (name "/SDO") (class "Default")
      (node (ref "R59") (pin "1") (pinfunction "1_1") (pintype "passive"))
      (node (ref "U3") (pin "43") (pinfunction "SDI_(ICMP)_43") (pintype "passive"))
    )
    (net (code "7") (name "GND") (class "Default")
      (node (ref "C13") (pin "1") (pinfunction "1_1") (pintype "passive"))
      (node (ref "C14") (pin "1") (pinfunction "1_1") (pintype "passive"))
      (node (ref "C15") (pin "1") (pinfunction "1_1") (pintype "passive"))
      (node (ref "C16") (pin "1") (pinfunction "1_1") (pintype "passive"))
      (node (ref "C17") (pin "1") (pinfunction "1_1") (pintype "passive"))
      (node (ref "C18") (pin "1") (pinfunction "1_1") (pintype "passive"))
      (node (ref "C19") (pin "1") (pinfunction "1_1") (pintype "passive"))
      (node (ref "C20") (pin "1") (pinfunction "1_1") (pintype "passive"))
      (node (ref "C21") (pin "1") (pinfunction "1_1") (pintype "passive"))
      (node (ref "C22") (pin "1") (pinfunction "1_1") (pintype "passive"))
      (node (ref "C23") (pin "1") (pinfunction "1_1") (pintype "passive"))
      (node (ref "C24") (pin "1") (pinfunction "1_1") (pintype "passive"))
      (node (ref "C25") (pin "1") (pinfunction "1_1") (pintype "passive"))
      (node (ref "C38") (pin "2") (pinfunction "2_2") (pintype "passive"))
      (node (ref "C39") (pin "2") (pinfunction "2_2") (pintype "passive"))
      (node (ref "C40") (pin "1") (pinfunction "1_1") (pintype "passive"))
      (node (ref "C41") (pin "1") (pinfunction "1_1") (pintype "passive"))
      (node (ref "C42") (pin "1") (pinfunction "1_1") (pintype "passive"))
      (node (ref "FB15") (pin "2") (pinfunction "2_2") (pintype "passive"))
      (node (ref "U3") (pin "30") (pinfunction "V-**_30") (pintype "passive"))
      (node (ref "U3") (pin "31") (pinfunction "V-_31") (pintype "passive"))
      (node (ref "U3") (pin "36") (pinfunction "DTEN_36") (pintype "passive"))
      (node (ref "U3") (pin "40") (pinfunction "ISOMD_40") (pintype "passive"))
      (node (ref "U3") (pin "45") (pinfunction "A0_45") (pintype "passive"))
      (node (ref "U3") (pin "46") (pinfunction "A1_46") (pintype "passive"))
      (node (ref "U3") (pin "47") (pinfunction "A2_47") (pintype "passive"))
      (node (ref "U3") (pin "48") (pinfunction "A3_48") (pintype "passive"))
    )
    (net (code "8") (name "Net-(D4-A)") (class "Default")
      (node (ref "D4") (pin "2") (pinfunction "A_2") (pintype "passive"))
      (node (ref "Q1") (pin "3") (pinfunction "DRAIN_3") (pintype "passive"))
      (node (ref "R20") (pin "2") (pinfunction "2_2") (pintype "passive"))
    )
    (net (code "9") (name "Net-(D4-K)") (class "Default")
      (node (ref "D4") (pin "1") (pinfunction "K_1") (pintype "passive"))
      (node (ref "R8") (pin "2") (pinfunction "2_2") (pintype "passive"))
    )
    (net (code "10") (name "Net-(D5-A)") (class "Default")
      (node (ref "D5") (pin "2") (pinfunction "A_2") (pintype "passive"))
      (node (ref "Q2") (pin "3") (pinfunction "DRAIN_3") (pintype "passive"))
      (node (ref "R21") (pin "2") (pinfunction "2_2") (pintype "passive"))
    )
    (net (code "11") (name "Net-(D5-K)") (class "Default")
      (node (ref "D5") (pin "1") (pinfunction "K_1") (pintype "passive"))
      (node (ref "R9") (pin "2") (pinfunction "2_2") (pintype "passive"))
    )
    (net (code "12") (name "Net-(D6-A)") (class "Default")
      (node (ref "D6") (pin "2") (pinfunction "A_2") (pintype "passive"))
      (node (ref "Q3") (pin "3") (pinfunction "DRAIN_3") (pintype "passive"))
      (node (ref "R22") (pin "2") (pinfunction "2_2") (pintype "passive"))
    )
    (net (code "13") (name "Net-(D6-K)") (class "Default")
      (node (ref "D6") (pin "1") (pinfunction "K_1") (pintype "passive"))
      (node (ref "R10") (pin "2") (pinfunction "2_2") (pintype "passive"))
    )
    (net (code "14") (name "Net-(D7-A)") (class "Default")
      (node (ref "D7") (pin "2") (pinfunction "A_2") (pintype "passive"))
      (node (ref "Q4") (pin "3") (pinfunction "DRAIN_3") (pintype "passive"))
      (node (ref "R23") (pin "2") (pinfunction "2_2") (pintype "passive"))
    )
    (net (code "15") (name "Net-(D7-K)") (class "Default")
      (node (ref "D7") (pin "1") (pinfunction "K_1") (pintype "passive"))
      (node (ref "R11") (pin "2") (pinfunction "2_2") (pintype "passive"))
    )
    (net (code "16") (name "Net-(D8-A)") (class "Default")
      (node (ref "D8") (pin "2") (pinfunction "A_2") (pintype "passive"))
      (node (ref "Q5") (pin "3") (pinfunction "DRAIN_3") (pintype "passive"))
      (node (ref "R24") (pin "2") (pinfunction "2_2") (pintype "passive"))
    )
    (net (code "17") (name "Net-(D8-K)") (class "Default")
      (node (ref "D8") (pin "1") (pinfunction "K_1") (pintype "passive"))
      (node (ref "R12") (pin "2") (pinfunction "2_2") (pintype "passive"))
    )
    (net (code "18") (name "Net-(D9-A)") (class "Default")
      (node (ref "D9") (pin "2") (pinfunction "A_2") (pintype "passive"))
      (node (ref "Q6") (pin "3") (pinfunction "DRAIN_3") (pintype "passive"))
      (node (ref "R25") (pin "2") (pinfunction "2_2") (pintype "passive"))
    )
    (net (code "19") (name "Net-(D9-K)") (class "Default")
      (node (ref "D9") (pin "1") (pinfunction "K_1") (pintype "passive"))
      (node (ref "R13") (pin "2") (pinfunction "2_2") (pintype "passive"))
    )
    (net (code "20") (name "Net-(D10-A)") (class "Default")
      (node (ref "D10") (pin "2") (pinfunction "A_2") (pintype "passive"))
      (node (ref "Q7") (pin "3") (pinfunction "DRAIN_3") (pintype "passive"))
      (node (ref "R26") (pin "2") (pinfunction "2_2") (pintype "passive"))
    )
    (net (code "21") (name "Net-(D10-K)") (class "Default")
      (node (ref "D10") (pin "1") (pinfunction "K_1") (pintype "passive"))
      (node (ref "R14") (pin "2") (pinfunction "2_2") (pintype "passive"))
    )
    (net (code "22") (name "Net-(D11-A)") (class "Default")
      (node (ref "D11") (pin "2") (pinfunction "A_2") (pintype "passive"))
      (node (ref "Q8") (pin "3") (pinfunction "DRAIN_3") (pintype "passive"))
      (node (ref "R27") (pin "2") (pinfunction "2_2") (pintype "passive"))
    )
    (net (code "23") (name "Net-(D11-K)") (class "Default")
      (node (ref "D11") (pin "1") (pinfunction "K_1") (pintype "passive"))
      (node (ref "R15") (pin "2") (pinfunction "2_2") (pintype "passive"))
    )
    (net (code "24") (name "Net-(D12-A)") (class "Default")
      (node (ref "D12") (pin "2") (pinfunction "A_2") (pintype "passive"))
      (node (ref "Q9") (pin "3") (pinfunction "DRAIN_3") (pintype "passive"))
      (node (ref "R28") (pin "2") (pinfunction "2_2") (pintype "passive"))
    )
    (net (code "25") (name "Net-(D12-K)") (class "Default")
      (node (ref "D12") (pin "1") (pinfunction "K_1") (pintype "passive"))
      (node (ref "R16") (pin "2") (pinfunction "2_2") (pintype "passive"))
    )
    (net (code "26") (name "Net-(D13-A)") (class "Default")
      (node (ref "D13") (pin "2") (pinfunction "A_2") (pintype "passive"))
      (node (ref "Q10") (pin "3") (pinfunction "DRAIN_3") (pintype "passive"))
      (node (ref "R29") (pin "2") (pinfunction "2_2") (pintype "passive"))
    )
    (net (code "27") (name "Net-(D13-K)") (class "Default")
      (node (ref "D13") (pin "1") (pinfunction "K_1") (pintype "passive"))
      (node (ref "R17") (pin "2") (pinfunction "2_2") (pintype "passive"))
    )
    (net (code "28") (name "Net-(D14-A)") (class "Default")
      (node (ref "D14") (pin "2") (pinfunction "A_2") (pintype "passive"))
      (node (ref "Q11") (pin "3") (pinfunction "DRAIN_3") (pintype "passive"))
      (node (ref "R30") (pin "2") (pinfunction "2_2") (pintype "passive"))
    )
    (net (code "29") (name "Net-(D14-K)") (class "Default")
      (node (ref "D14") (pin "1") (pinfunction "K_1") (pintype "passive"))
      (node (ref "R18") (pin "2") (pinfunction "2_2") (pintype "passive"))
    )
    (net (code "30") (name "Net-(D15-A)") (class "Default")
      (node (ref "D15") (pin "2") (pinfunction "A_2") (pintype "passive"))
      (node (ref "Q12") (pin "3") (pinfunction "DRAIN_3") (pintype "passive"))
      (node (ref "R31") (pin "2") (pinfunction "2_2") (pintype "passive"))
    )
    (net (code "31") (name "Net-(D15-K)") (class "Default")
      (node (ref "D15") (pin "1") (pinfunction "K_1") (pintype "passive"))
      (node (ref "R19") (pin "2") (pinfunction "2_2") (pintype "passive"))
    )
    (net (code "32") (name "Net-(FB1-Pad1)") (class "Default")
      (node (ref "FB1") (pin "1") (pinfunction "1_1") (pintype "passive"))
      (node (ref "FB2") (pin "1") (pinfunction "1_1") (pintype "passive"))
      (node (ref "J4") (pin "1") (pinfunction "1_1") (pintype "passive"))
      (node (ref "J5") (pin "1") (pinfunction "1_1") (pintype "passive"))
      (node (ref "J5") (pin "2") (pinfunction "2_2") (pintype "passive"))
    )
    (net (code "33") (name "Net-(FB3-Pad1)") (class "Default")
      (node (ref "FB3") (pin "1") (pinfunction "1_1") (pintype "passive"))
      (node (ref "J4") (pin "2") (pinfunction "2_2") (pintype "passive"))
      (node (ref "J5") (pin "3") (pinfunction "3_3") (pintype "passive"))
      (node (ref "J5") (pin "4") (pinfunction "4_4") (pintype "passive"))
    )
    (net (code "34") (name "Net-(FB4-Pad1)") (class "Default")
      (node (ref "FB4") (pin "1") (pinfunction "1_1") (pintype "passive"))
      (node (ref "J4") (pin "3") (pinfunction "3_3") (pintype "passive"))
      (node (ref "J5") (pin "5") (pinfunction "5_5") (pintype "passive"))
      (node (ref "J5") (pin "6") (pinfunction "6_6") (pintype "passive"))
    )
    (net (code "35") (name "Net-(FB5-Pad1)") (class "Default")
      (node (ref "FB5") (pin "1") (pinfunction "1_1") (pintype "passive"))
      (node (ref "J4") (pin "4") (pinfunction "4_4") (pintype "passive"))
      (node (ref "J5") (pin "7") (pinfunction "7_7") (pintype "passive"))
      (node (ref "J5") (pin "8") (pinfunction "8_8") (pintype "passive"))
    )
    (net (code "36") (name "Net-(FB6-Pad1)") (class "Default")
      (node (ref "FB6") (pin "1") (pinfunction "1_1") (pintype "passive"))
      (node (ref "J4") (pin "5") (pinfunction "5_5") (pintype "passive"))
      (node (ref "J5") (pin "10") (pinfunction "10_10") (pintype "passive"))
      (node (ref "J5") (pin "9") (pinfunction "9_9") (pintype "passive"))
    )
    (net (code "37") (name "Net-(FB7-Pad1)") (class "Default")
      (node (ref "FB7") (pin "1") (pinfunction "1_1") (pintype "passive"))
      (node (ref "J4") (pin "6") (pinfunction "6_6") (pintype "passive"))
    )
    (net (code "38") (name "Net-(FB8-Pad1)") (class "Default")
      (node (ref "FB8") (pin "1") (pinfunction "1_1") (pintype "passive"))
      (node (ref "J4") (pin "7") (pinfunction "7_7") (pintype "passive"))
    )
    (net (code "39") (name "Net-(FB9-Pad1)") (class "Default")
      (node (ref "FB9") (pin "1") (pinfunction "1_1") (pintype "passive"))
      (node (ref "J4") (pin "8") (pinfunction "8_8") (pintype "passive"))
    )
    (net (code "40") (name "Net-(FB10-Pad1)") (class "Default")
      (node (ref "FB10") (pin "1") (pinfunction "1_1") (pintype "passive"))
      (node (ref "J4") (pin "9") (pinfunction "9_9") (pintype "passive"))
    )
    (net (code "41") (name "Net-(FB11-Pad1)") (class "Default")
      (node (ref "FB11") (pin "1") (pinfunction "1_1") (pintype "passive"))
      (node (ref "J4") (pin "10") (pinfunction "10_10") (pintype "passive"))
    )
    (net (code "42") (name "Net-(FB12-Pad1)") (class "Default")
      (node (ref "FB12") (pin "1") (pinfunction "1_1") (pintype "passive"))
      (node (ref "J4") (pin "11") (pinfunction "11_11") (pintype "passive"))
    )
    (net (code "43") (name "Net-(FB13-Pad1)") (class "Default")
      (node (ref "FB13") (pin "1") (pinfunction "1_1") (pintype "passive"))
      (node (ref "J4") (pin "12") (pinfunction "12_12") (pintype "passive"))
    )
    (net (code "44") (name "Net-(FB14-Pad1)") (class "Default")
      (node (ref "FB14") (pin "1") (pinfunction "1_1") (pintype "passive"))
      (node (ref "FB15") (pin "1") (pinfunction "1_1") (pintype "passive"))
      (node (ref "J4") (pin "13") (pinfunction "13_13") (pintype "passive"))
    )
    (net (code "45") (name "Net-(FB14-Pad2)") (class "Default")
      (node (ref "FB14") (pin "2") (pinfunction "2_2") (pintype "passive"))
      (node (ref "R19") (pin "1") (pinfunction "1_1") (pintype "passive"))
      (node (ref "R31") (pin "1") (pinfunction "1_1") (pintype "passive"))
      (node (ref "R56") (pin "1") (pinfunction "1_1") (pintype "passive"))
    )
    (net (code "46") (name "Net-(Q1-GATE)") (class "Default")
      (node (ref "Q1") (pin "1") (pinfunction "GATE_1") (pintype "passive"))
      (node (ref "R32") (pin "1") (pinfunction "1_1") (pintype "passive"))
    )
    (net (code "47") (name "Net-(Q1-SOURCE)") (class "Default")
      (node (ref "FB2") (pin "2") (pinfunction "2_2") (pintype "passive"))
      (node (ref "Q1") (pin "2") (pinfunction "SOURCE_2") (pintype "passive"))
      (node (ref "R44") (pin "1") (pinfunction "1_1") (pintype "passive"))
    )
    (net (code "48") (name "Net-(Q2-GATE)") (class "Default")
      (node (ref "Q2") (pin "1") (pinfunction "GATE_1") (pintype "passive"))
      (node (ref "R33") (pin "1") (pinfunction "1_1") (pintype "passive"))
    )
    (net (code "49") (name "Net-(Q2-SOURCE)") (class "Default")
      (node (ref "FB3") (pin "2") (pinfunction "2_2") (pintype "passive"))
      (node (ref "Q2") (pin "2") (pinfunction "SOURCE_2") (pintype "passive"))
      (node (ref "R20") (pin "1") (pinfunction "1_1") (pintype "passive"))
      (node (ref "R45") (pin "1") (pinfunction "1_1") (pintype "passive"))
      (node (ref "R8") (pin "1") (pinfunction "1_1") (pintype "passive"))
    )
    (net (code "50") (name "Net-(Q3-GATE)") (class "Default")
      (node (ref "Q3") (pin "1") (pinfunction "GATE_1") (pintype "passive"))
      (node (ref "R34") (pin "1") (pinfunction "1_1") (pintype "passive"))
    )
    (net (code "51") (name "Net-(Q3-SOURCE)") (class "Default")
      (node (ref "FB4") (pin "2") (pinfunction "2_2") (pintype "passive"))
      (node (ref "Q3") (pin "2") (pinfunction "SOURCE_2") (pintype "passive"))
      (node (ref "R21") (pin "1") (pinfunction "1_1") (pintype "passive"))
      (node (ref "R46") (pin "1") (pinfunction "1_1") (pintype "passive"))
      (node (ref "R9") (pin "1") (pinfunction "1_1") (pintype "passive"))
    )
    (net (code "52") (name "Net-(Q4-GATE)") (class "Default")
      (node (ref "Q4") (pin "1") (pinfunction "GATE_1") (pintype "passive"))
      (node (ref "R35") (pin "1") (pinfunction "1_1") (pintype "passive"))
    )
    (net (code "53") (name "Net-(Q4-SOURCE)") (class "Default")
      (node (ref "FB5") (pin "2") (pinfunction "2_2") (pintype "passive"))
      (node (ref "Q4") (pin "2") (pinfunction "SOURCE_2") (pintype "passive"))
      (node (ref "R10") (pin "1") (pinfunction "1_1") (pintype "passive"))
      (node (ref "R22") (pin "1") (pinfunction "1_1") (pintype "passive"))
      (node (ref "R47") (pin "1") (pinfunction "1_1") (pintype "passive"))
    )
    (net (code "54") (name "Net-(Q5-GATE)") (class "Default")
      (node (ref "Q5") (pin "1") (pinfunction "GATE_1") (pintype "passive"))
      (node (ref "R36") (pin "1") (pinfunction "1_1") (pintype "passive"))
    )
    (net (code "55") (name "Net-(Q5-SOURCE)") (class "Default")
      (node (ref "FB6") (pin "2") (pinfunction "2_2") (pintype "passive"))
      (node (ref "Q5") (pin "2") (pinfunction "SOURCE_2") (pintype "passive"))
      (node (ref "R11") (pin "1") (pinfunction "1_1") (pintype "passive"))
      (node (ref "R23") (pin "1") (pinfunction "1_1") (pintype "passive"))
      (node (ref "R48") (pin "1") (pinfunction "1_1") (pintype "passive"))
    )
    (net (code "56") (name "Net-(Q6-GATE)") (class "Default")
      (node (ref "Q6") (pin "1") (pinfunction "GATE_1") (pintype "passive"))
      (node (ref "R37") (pin "1") (pinfunction "1_1") (pintype "passive"))
    )
    (net (code "57") (name "Net-(Q6-SOURCE)") (class "Default")
      (node (ref "FB7") (pin "2") (pinfunction "2_2") (pintype "passive"))
      (node (ref "Q6") (pin "2") (pinfunction "SOURCE_2") (pintype "passive"))
      (node (ref "R12") (pin "1") (pinfunction "1_1") (pintype "passive"))
      (node (ref "R24") (pin "1") (pinfunction "1_1") (pintype "passive"))
      (node (ref "R49") (pin "1") (pinfunction "1_1") (pintype "passive"))
    )
    (net (code "58") (name "Net-(Q7-GATE)") (class "Default")
      (node (ref "Q7") (pin "1") (pinfunction "GATE_1") (pintype "passive"))
      (node (ref "R38") (pin "1") (pinfunction "1_1") (pintype "passive"))
    )
    (net (code "59") (name "Net-(Q7-SOURCE)") (class "Default")
      (node (ref "FB8") (pin "2") (pinfunction "2_2") (pintype "passive"))
      (node (ref "Q7") (pin "2") (pinfunction "SOURCE_2") (pintype "passive"))
      (node (ref "R13") (pin "1") (pinfunction "1_1") (pintype "passive"))
      (node (ref "R25") (pin "1") (pinfunction "1_1") (pintype "passive"))
      (node (ref "R50") (pin "1") (pinfunction "1_1") (pintype "passive"))
    )
    (net (code "60") (name "Net-(Q8-GATE)") (class "Default")
      (node (ref "Q8") (pin "1") (pinfunction "GATE_1") (pintype "passive"))
      (node (ref "R39") (pin "1") (pinfunction "1_1") (pintype "passive"))
    )
    (net (code "61") (name "Net-(Q8-SOURCE)") (class "Default")
      (node (ref "FB9") (pin "2") (pinfunction "2_2") (pintype "passive"))
      (node (ref "Q8") (pin "2") (pinfunction "SOURCE_2") (pintype "passive"))
      (node (ref "R14") (pin "1") (pinfunction "1_1") (pintype "passive"))
      (node (ref "R26") (pin "1") (pinfunction "1_1") (pintype "passive"))
      (node (ref "R51") (pin "1") (pinfunction "1_1") (pintype "passive"))
    )
    (net (code "62") (name "Net-(Q9-GATE)") (class "Default")
      (node (ref "Q9") (pin "1") (pinfunction "GATE_1") (pintype "passive"))
      (node (ref "R40") (pin "1") (pinfunction "1_1") (pintype "passive"))
    )
    (net (code "63") (name "Net-(Q9-SOURCE)") (class "Default")
      (node (ref "FB10") (pin "2") (pinfunction "2_2") (pintype "passive"))
      (node (ref "Q9") (pin "2") (pinfunction "SOURCE_2") (pintype "passive"))
      (node (ref "R15") (pin "1") (pinfunction "1_1") (pintype "passive"))
      (node (ref "R27") (pin "1") (pinfunction "1_1") (pintype "passive"))
      (node (ref "R52") (pin "1") (pinfunction "1_1") (pintype "passive"))
    )
    (net (code "64") (name "Net-(Q10-GATE)") (class "Default")
      (node (ref "Q10") (pin "1") (pinfunction "GATE_1") (pintype "passive"))
      (node (ref "R41") (pin "1") (pinfunction "1_1") (pintype "passive"))
    )
    (net (code "65") (name "Net-(Q10-SOURCE)") (class "Default")
      (node (ref "FB11") (pin "2") (pinfunction "2_2") (pintype "passive"))
      (node (ref "Q10") (pin "2") (pinfunction "SOURCE_2") (pintype "passive"))
      (node (ref "R16") (pin "1") (pinfunction "1_1") (pintype "passive"))
      (node (ref "R28") (pin "1") (pinfunction "1_1") (pintype "passive"))
      (node (ref "R53") (pin "1") (pinfunction "1_1") (pintype "passive"))
    )
    (net (code "66") (name "Net-(Q11-GATE)") (class "Default")
      (node (ref "Q11") (pin "1") (pinfunction "GATE_1") (pintype "passive"))
      (node (ref "R42") (pin "1") (pinfunction "1_1") (pintype "passive"))
    )
    (net (code "67") (name "Net-(Q11-SOURCE)") (class "Default")
      (node (ref "FB12") (pin "2") (pinfunction "2_2") (pintype "passive"))
      (node (ref "Q11") (pin "2") (pinfunction "SOURCE_2") (pintype "passive"))
      (node (ref "R17") (pin "1") (pinfunction "1_1") (pintype "passive"))
      (node (ref "R29") (pin "1") (pinfunction "1_1") (pintype "passive"))
      (node (ref "R54") (pin "1") (pinfunction "1_1") (pintype "passive"))
    )
    (net (code "68") (name "Net-(Q12-GATE)") (class "Default")
      (node (ref "Q12") (pin "1") (pinfunction "GATE_1") (pintype "passive"))
      (node (ref "R43") (pin "1") (pinfunction "1_1") (pintype "passive"))
    )
    (net (code "69") (name "Net-(Q12-SOURCE)") (class "Default")
      (node (ref "FB13") (pin "2") (pinfunction "2_2") (pintype "passive"))
      (node (ref "Q12") (pin "2") (pinfunction "SOURCE_2") (pintype "passive"))
      (node (ref "R18") (pin "1") (pinfunction "1_1") (pintype "passive"))
      (node (ref "R30") (pin "1") (pinfunction "1_1") (pintype "passive"))
      (node (ref "R55") (pin "1") (pinfunction "1_1") (pintype "passive"))
    )
    (net (code "70") (name "Net-(U3-C0)") (class "Default")
      (node (ref "C25") (pin "2") (pinfunction "2_2") (pintype "passive"))
      (node (ref "C37") (pin "1") (pinfunction "1_1") (pintype "passive"))
      (node (ref "R56") (pin "2") (pinfunction "2_2") (pintype "passive"))
      (node (ref "U3") (pin "26") (pinfunction "C0_26") (pintype "passive"))
    )
    (net (code "71") (name "Net-(U3-C1)") (class "Default")
      (node (ref "C24") (pin "2") (pinfunction "2_2") (pintype "passive"))
      (node (ref "C36") (pin "1") (pinfunction "1_1") (pintype "passive"))
      (node (ref "C37") (pin "2") (pinfunction "2_2") (pintype "passive"))
      (node (ref "R55") (pin "2") (pinfunction "2_2") (pintype "passive"))
      (node (ref "U3") (pin "24") (pinfunction "C1_24") (pintype "passive"))
    )
    (net (code "72") (name "Net-(U3-C2)") (class "Default")
      (node (ref "C23") (pin "2") (pinfunction "2_2") (pintype "passive"))
      (node (ref "C35") (pin "1") (pinfunction "1_1") (pintype "passive"))
      (node (ref "C36") (pin "2") (pinfunction "2_2") (pintype "passive"))
      (node (ref "R54") (pin "2") (pinfunction "2_2") (pintype "passive"))
      (node (ref "U3") (pin "22") (pinfunction "C2_22") (pintype "passive"))
    )
    (net (code "73") (name "Net-(U3-C3)") (class "Default")
      (node (ref "C22") (pin "2") (pinfunction "2_2") (pintype "passive"))
      (node (ref "C34") (pin "1") (pinfunction "1_1") (pintype "passive"))
      (node (ref "C35") (pin "2") (pinfunction "2_2") (pintype "passive"))
      (node (ref "R53") (pin "2") (pinfunction "2_2") (pintype "passive"))
      (node (ref "U3") (pin "20") (pinfunction "C3_20") (pintype "passive"))
    )
    (net (code "74") (name "Net-(U3-C4)") (class "Default")
      (node (ref "C21") (pin "2") (pinfunction "2_2") (pintype "passive"))
      (node (ref "C33") (pin "1") (pinfunction "1_1") (pintype "passive"))
      (node (ref "C34") (pin "2") (pinfunction "2_2") (pintype "passive"))
      (node (ref "R52") (pin "2") (pinfunction "2_2") (pintype "passive"))
      (node (ref "U3") (pin "18") (pinfunction "C4_18") (pintype "passive"))
    )
    (net (code "75") (name "Net-(U3-C5)") (class "Default")
      (node (ref "C20") (pin "2") (pinfunction "2_2") (pintype "passive"))
      (node (ref "C32") (pin "1") (pinfunction "1_1") (pintype "passive"))
      (node (ref "C33") (pin "2") (pinfunction "2_2") (pintype "passive"))
      (node (ref "R51") (pin "2") (pinfunction "2_2") (pintype "passive"))
      (node (ref "U3") (pin "16") (pinfunction "C5_16") (pintype "passive"))
    )
    (net (code "76") (name "Net-(U3-C6)") (class "Default")
      (node (ref "C19") (pin "2") (pinfunction "2_2") (pintype "passive"))
      (node (ref "C26") (pin "1") (pinfunction "1_1") (pintype "passive"))
      (node (ref "C32") (pin "2") (pinfunction "2_2") (pintype "passive"))
      (node (ref "R50") (pin "2") (pinfunction "2_2") (pintype "passive"))
      (node (ref "U3") (pin "14") (pinfunction "C6_14") (pintype "passive"))
    )
    (net (code "77") (name "Net-(U3-C7)") (class "Default")
      (node (ref "C18") (pin "2") (pinfunction "2_2") (pintype "passive"))
      (node (ref "C26") (pin "2") (pinfunction "2_2") (pintype "passive"))
      (node (ref "C31") (pin "1") (pinfunction "1_1") (pintype "passive"))
      (node (ref "R49") (pin "2") (pinfunction "2_2") (pintype "passive"))
      (node (ref "U3") (pin "12") (pinfunction "C7_12") (pintype "passive"))
    )
    (net (code "78") (name "Net-(U3-C8)") (class "Default")
      (node (ref "C17") (pin "2") (pinfunction "2_2") (pintype "passive"))
      (node (ref "C30") (pin "1") (pinfunction "1_1") (pintype "passive"))
      (node (ref "C31") (pin "2") (pinfunction "2_2") (pintype "passive"))
      (node (ref "R48") (pin "2") (pinfunction "2_2") (pintype "passive"))
      (node (ref "U3") (pin "10") (pinfunction "C8_10") (pintype "passive"))
    )
    (net (code "79") (name "Net-(U3-C9)") (class "Default")
      (node (ref "C16") (pin "2") (pinfunction "2_2") (pintype "passive"))
      (node (ref "C29") (pin "1") (pinfunction "1_1") (pintype "passive"))
      (node (ref "C30") (pin "2") (pinfunction "2_2") (pintype "passive"))
      (node (ref "R47") (pin "2") (pinfunction "2_2") (pintype "passive"))
      (node (ref "U3") (pin "8") (pinfunction "C9_8") (pintype "passive"))
    )
    (net (code "80") (name "Net-(U3-C10)") (class "Default")
      (node (ref "C15") (pin "2") (pinfunction "2_2") (pintype "passive"))
      (node (ref "C28") (pin "1") (pinfunction "1_1") (pintype "passive"))
      (node (ref "C29") (pin "2") (pinfunction "2_2") (pintype "passive"))
      (node (ref "R46") (pin "2") (pinfunction "2_2") (pintype "passive"))
      (node (ref "U3") (pin "6") (pinfunction "C10_6") (pintype "passive"))
    )
    (net (code "81") (name "Net-(U3-C11)") (class "Default")
      (node (ref "C14") (pin "2") (pinfunction "2_2") (pintype "passive"))
      (node (ref "C27") (pin "1") (pinfunction "1_1") (pintype "passive"))
      (node (ref "C28") (pin "2") (pinfunction "2_2") (pintype "passive"))
      (node (ref "R45") (pin "2") (pinfunction "2_2") (pintype "passive"))
      (node (ref "U3") (pin "4") (pinfunction "C11_4") (pintype "passive"))
    )
    (net (code "82") (name "Net-(U3-C12)") (class "Default")
      (node (ref "C13") (pin "2") (pinfunction "2_2") (pintype "passive"))
      (node (ref "C27") (pin "2") (pinfunction "2_2") (pintype "passive"))
      (node (ref "R44") (pin "2") (pinfunction "2_2") (pintype "passive"))
      (node (ref "U3") (pin "2") (pinfunction "C12_2") (pintype "passive"))
    )
    (net (code "83") (name "Net-(U3-S1)") (class "Default")
      (node (ref "R43") (pin "2") (pinfunction "2_2") (pintype "passive"))
      (node (ref "U3") (pin "25") (pinfunction "S1_25") (pintype "passive"))
    )
    (net (code "84") (name "Net-(U3-S2)") (class "Default")
      (node (ref "R42") (pin "2") (pinfunction "2_2") (pintype "passive"))
      (node (ref "U3") (pin "23") (pinfunction "S2_23") (pintype "passive"))
    )
    (net (code "85") (name "Net-(U3-S3)") (class "Default")
      (node (ref "R41") (pin "2") (pinfunction "2_2") (pintype "passive"))
      (node (ref "U3") (pin "21") (pinfunction "S3_21") (pintype "passive"))
    )
    (net (code "86") (name "Net-(U3-S4)") (class "Default")
      (node (ref "R40") (pin "2") (pinfunction "2_2") (pintype "passive"))
      (node (ref "U3") (pin "19") (pinfunction "S4_19") (pintype "passive"))
    )
    (net (code "87") (name "Net-(U3-S5)") (class "Default")
      (node (ref "R39") (pin "2") (pinfunction "2_2") (pintype "passive"))
      (node (ref "U3") (pin "17") (pinfunction "S5_17") (pintype "passive"))
    )
    (net (code "88") (name "Net-(U3-S6)") (class "Default")
      (node (ref "R38") (pin "2") (pinfunction "2_2") (pintype "passive"))
      (node (ref "U3") (pin "15") (pinfunction "S6_15") (pintype "passive"))
    )
    (net (code "89") (name "Net-(U3-S7)") (class "Default")
      (node (ref "R37") (pin "2") (pinfunction "2_2") (pintype "passive"))
      (node (ref "U3") (pin "13") (pinfunction "S7_13") (pintype "passive"))
    )
    (net (code "90") (name "Net-(U3-S8)") (class "Default")
      (node (ref "R36") (pin "2") (pinfunction "2_2") (pintype "passive"))
      (node (ref "U3") (pin "11") (pinfunction "S8_11") (pintype "passive"))
    )
    (net (code "91") (name "Net-(U3-S9)") (class "Default")
      (node (ref "R35") (pin "2") (pinfunction "2_2") (pintype "passive"))
      (node (ref "U3") (pin "9") (pinfunction "S9_9") (pintype "passive"))
    )
    (net (code "92") (name "Net-(U3-S10)") (class "Default")
      (node (ref "R34") (pin "2") (pinfunction "2_2") (pintype "passive"))
      (node (ref "U3") (pin "7") (pinfunction "S10_7") (pintype "passive"))
    )
    (net (code "93") (name "Net-(U3-S11)") (class "Default")
      (node (ref "R33") (pin "2") (pinfunction "2_2") (pintype "passive"))
      (node (ref "U3") (pin "5") (pinfunction "S11_5") (pintype "passive"))
    )
    (net (code "94") (name "Net-(U3-S12)") (class "Default")
      (node (ref "R32") (pin "2") (pinfunction "2_2") (pintype "passive"))
      (node (ref "U3") (pin "3") (pinfunction "S12_3") (pintype "passive"))
    )
    (net (code "95") (name "Net-(U3-Vref1)") (class "Default")
      (node (ref "C41") (pin "2") (pinfunction "2_2") (pintype "passive"))
      (node (ref "U3") (pin "35") (pinfunction "Vref1_35") (pintype "passive"))
    )
    (net (code "96") (name "Net-(U3-Vref2)") (class "Default")
      (node (ref "C40") (pin "2") (pinfunction "2_2") (pintype "passive"))
      (node (ref "U3") (pin "34") (pinfunction "Vref2_34") (pintype "passive"))
    )
    (net (code "97") (name "unconnected-(U3-DRIVE-Pad38)") (class "Default")
      (node (ref "U3") (pin "38") (pinfunction "DRIVE_38") (pintype "passive"))
    )
    (net (code "98") (name "unconnected-(U3-GPIO1-Pad27)") (class "Default")
      (node (ref "U3") (pin "27") (pinfunction "GPIO1_27") (pintype "passive"))
    )
    (net (code "99") (name "unconnected-(U3-GPIO2-Pad28)") (class "Default")
      (node (ref "U3") (pin "28") (pinfunction "GPIO2_28") (pintype "passive"))
    )
    (net (code "100") (name "unconnected-(U3-GPIO3-Pad29)") (class "Default")
      (node (ref "U3") (pin "29") (pinfunction "GPIO3_29") (pintype "passive"))
    )
    (net (code "101") (name "unconnected-(U3-GPIO4-Pad32)") (class "Default")
      (node (ref "U3") (pin "32") (pinfunction "GPIO4_32") (pintype "passive"))
    )
    (net (code "102") (name "unconnected-(U3-GPIO5-Pad33)") (class "Default")
      (node (ref "U3") (pin "33") (pinfunction "GPIO5_33") (pintype "passive"))
    )
  )
)
